# SCH_FletchVR_2024-06-24.net
KiCad netlist of a schematic drawn in EasyEDA
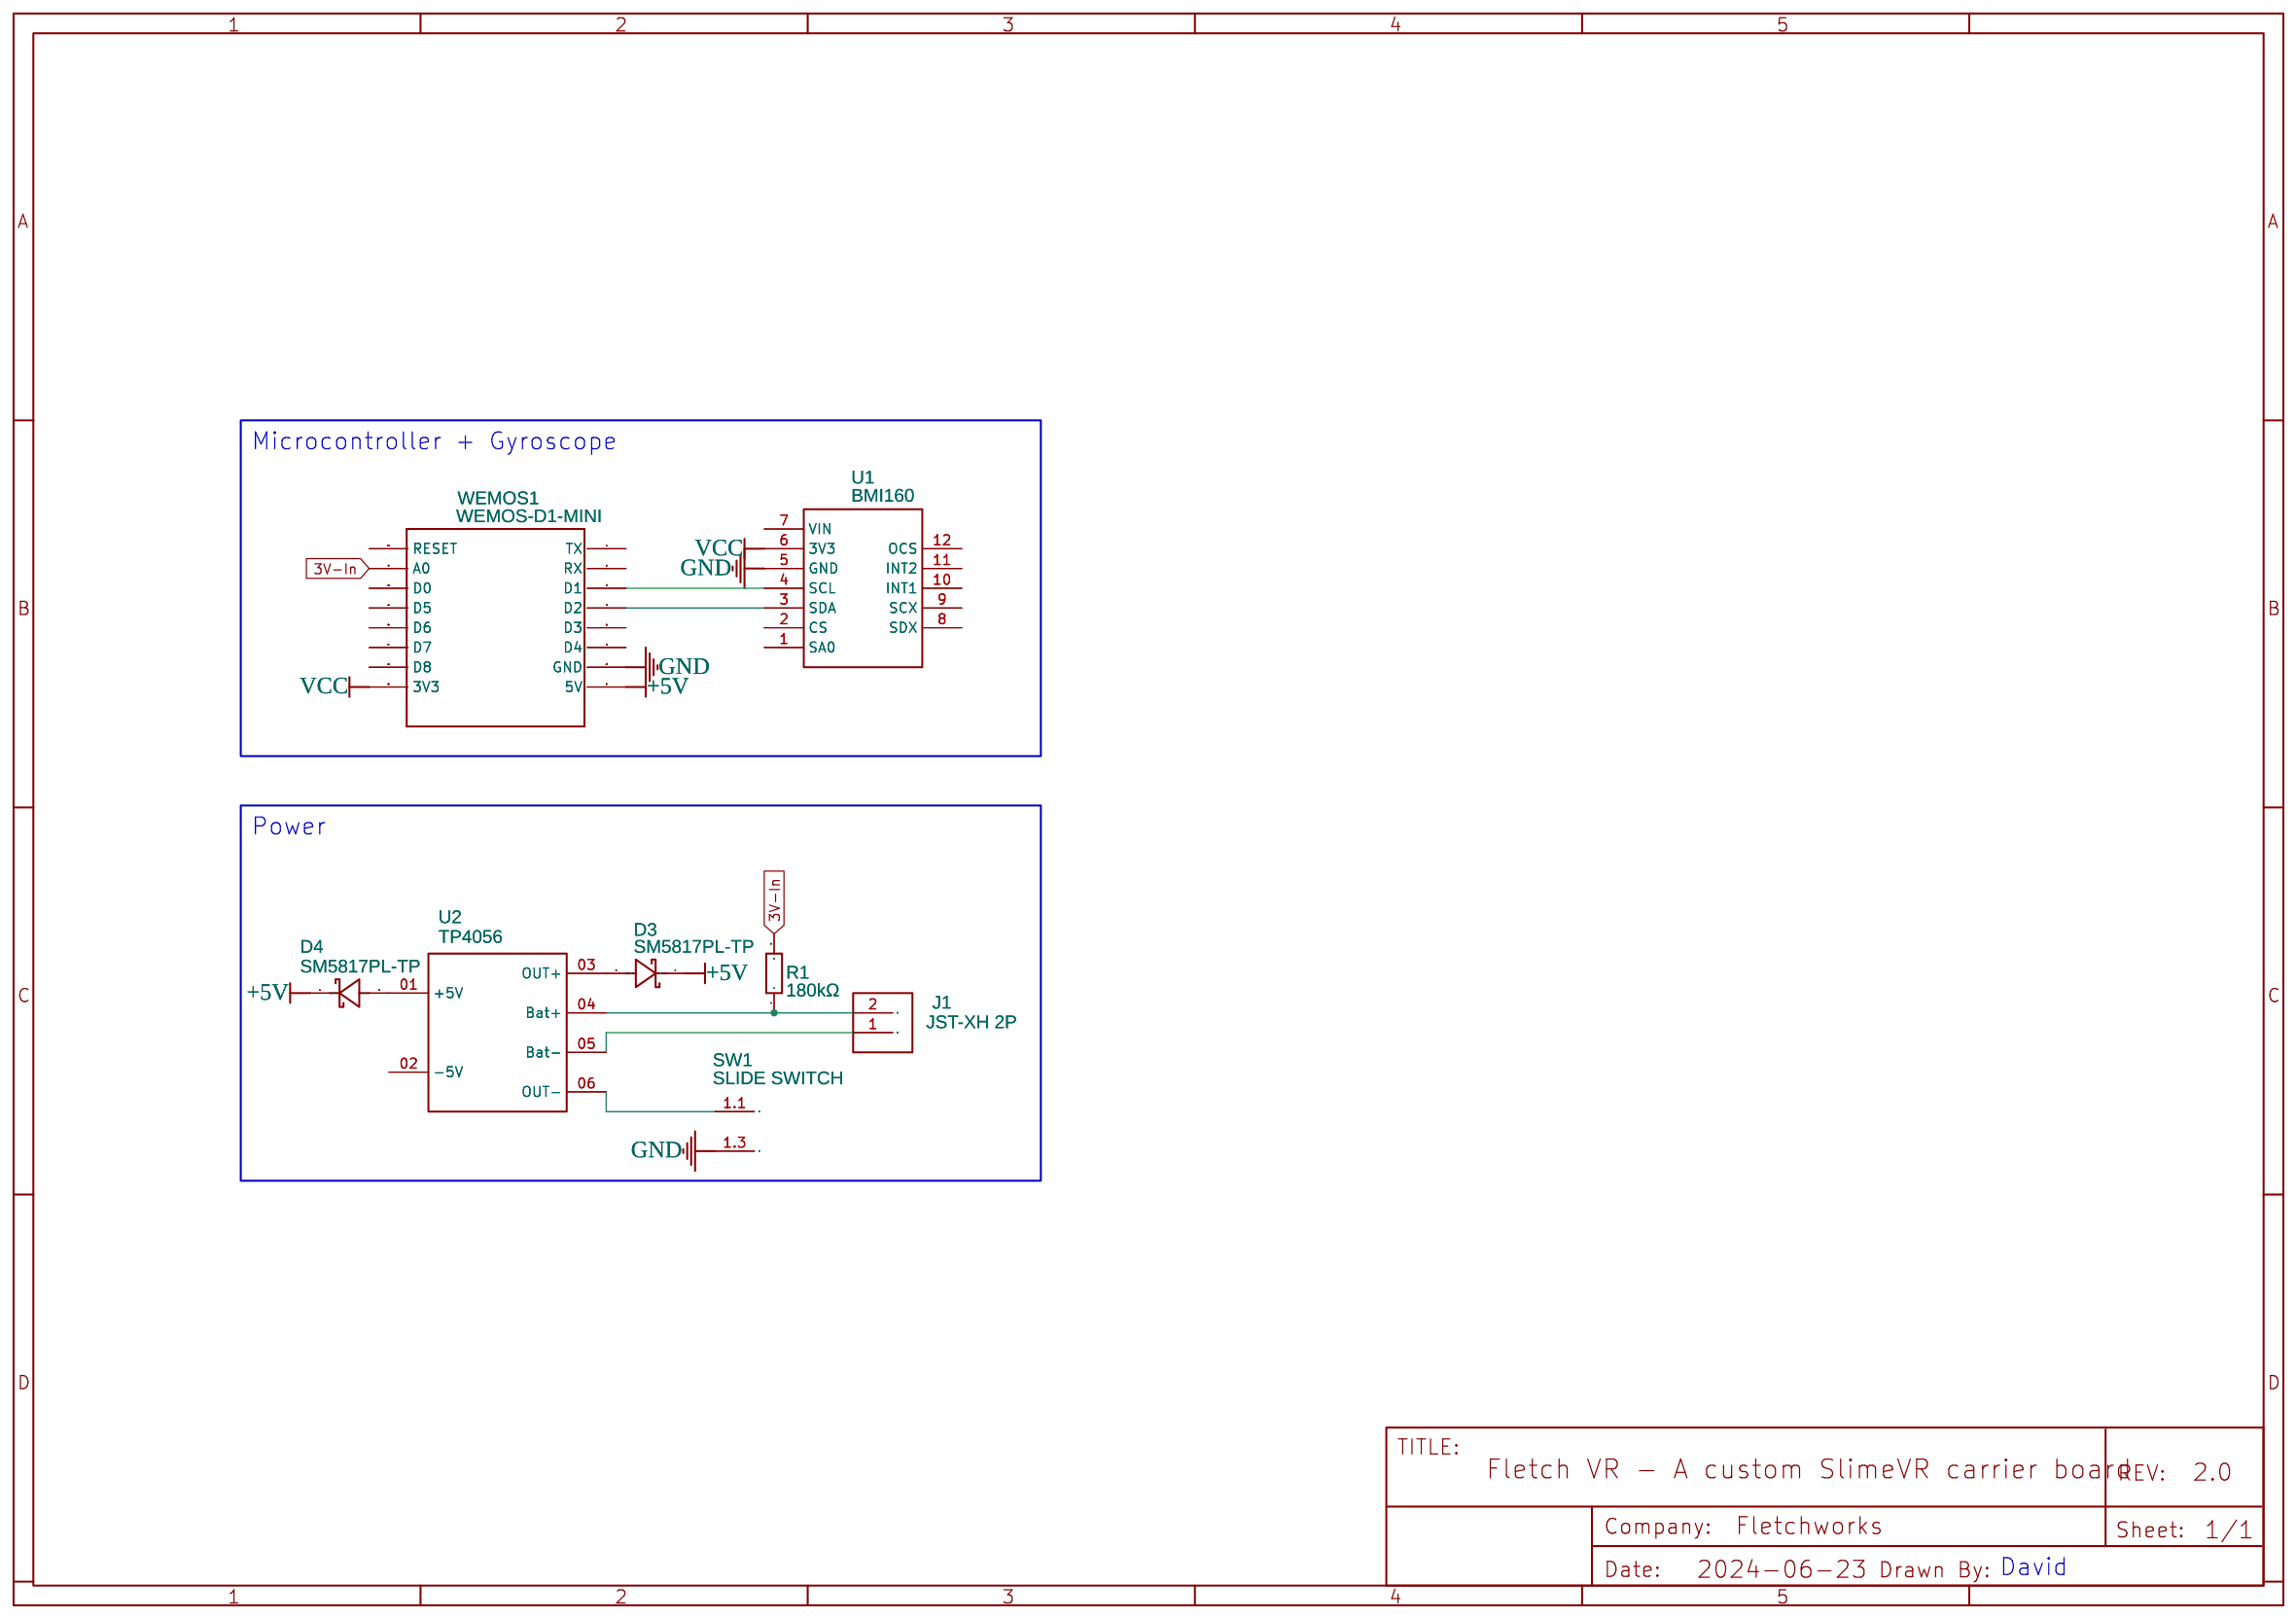
[diagram p0: schematic sheet]

(export (version "E")
  (design (tool "Eeschema 10.0.6"))
  (components
    (comp (ref "D3")
      (value "SM5817PL-TP")
      (fields (field (name "Manufacturer") "MCC(美微科)"))
      (libsource (lib "") (part "SM5817PL-TP"))
    )
    (comp (ref "D4")
      (value "SM5817PL-TP")
      (fields (field (name "Manufacturer") "MCC(美微科)"))
      (libsource (lib "") (part "SM5817PL-TP_1"))
    )
    (comp (ref "J1") (value "JST-XH 2P") (libsource (lib "") (part "JST-XH 2P")))
    (comp (ref "R1")
      (value "180kΩ")
      (fields
        (field (name "Manufacturer Part") "RMCF0402JT180K")
        (field (name "Manufacturer") "SEI(Stackpole Electronics Inc.)")
      )
      (libsource (lib "") (part "RMCF0402JT180K"))
    )
    (comp (ref "SW1")
      (value "SLIDE SWITCH")
      (fields (field (name "Manufacturer Part") "SS22F32"))
      (libsource (lib "") (part "SLIDE SWITCH 2P2T - SS22F32 PCB SLIME"))
    )
    (comp (ref "U1") (value "BMI160") (libsource (lib "") (part "BMI160")))
    (comp (ref "U2") (value "TP4056") (libsource (lib "") (part "TP4056 Symbole (modul)")))
    (comp (ref "WEMOS1") (value "WEMOS-D1-MINI") (libsource (lib "") (part "WEMOS-D1-MINI")))
  )
  (nets
    (net (code "1") (name "+5V") (class "Default")
      (node (ref "D3") (pin "1") (pinfunction "C_1") (pintype "unspecified"))
      (node (ref "D4") (pin "1") (pinfunction "C_1") (pintype "unspecified"))
      (node (ref "WEMOS1") (pin "5V") (pinfunction "5V_5V") (pintype "bidirectional"))
    )
    (net (code "2") (name "3V-In") (class "Default")
      (node (ref "R1") (pin "2") (pinfunction "2_2") (pintype "unspecified"))
      (node (ref "WEMOS1") (pin "A0") (pinfunction "A0_A0") (pintype "bidirectional"))
    )
    (net (code "3") (name "GND") (class "Default")
      (node (ref "SW1") (pin "1.3") (pinfunction "2_1.3") (pintype "unspecified"))
      (node (ref "U1") (pin "5") (pinfunction "GND_5") (pintype "unspecified"))
      (node (ref "WEMOS1") (pin "GND") (pinfunction "GND_GND") (pintype "bidirectional"))
    )
    (net (code "4") (name "Net-(D3-A)") (class "Default")
      (node (ref "D3") (pin "2") (pinfunction "A_2") (pintype "unspecified"))
      (node (ref "U2") (pin "03") (pinfunction "OUT+_03") (pintype "unspecified"))
    )
    (net (code "5") (name "Net-(D4-A)") (class "Default")
      (node (ref "D4") (pin "2") (pinfunction "A_2") (pintype "unspecified"))
      (node (ref "U2") (pin "01") (pinfunction "+5V_01") (pintype "unspecified"))
    )
    (net (code "6") (name "Net-(SW1-1)") (class "Default")
      (node (ref "SW1") (pin "1.1") (pinfunction "1_1.1") (pintype "unspecified"))
      (node (ref "U2") (pin "06") (pinfunction "OUT-_06") (pintype "unspecified"))
    )
    (net (code "7") (name "Net-(U1-SCL)") (class "Default")
      (node (ref "U1") (pin "4") (pinfunction "SCL_4") (pintype "unspecified"))
      (node (ref "WEMOS1") (pin "D1") (pinfunction "D1_D1") (pintype "bidirectional"))
    )
    (net (code "8") (name "Net-(U1-SDA)") (class "Default")
      (node (ref "U1") (pin "3") (pinfunction "SDA_3") (pintype "unspecified"))
      (node (ref "WEMOS1") (pin "D2") (pinfunction "D2_D2") (pintype "bidirectional"))
    )
    (net (code "9") (name "Net-(U2-Bat+)") (class "Default")
      (node (ref "J1") (pin "2") (pinfunction "2_2") (pintype "unspecified"))
      (node (ref "R1") (pin "1") (pinfunction "1_1") (pintype "unspecified"))
      (node (ref "U2") (pin "04") (pinfunction "Bat+_04") (pintype "unspecified"))
    )
    (net (code "10") (name "Net-(U2-Bat-)") (class "Default")
      (node (ref "J1") (pin "1") (pinfunction "1_1") (pintype "unspecified"))
      (node (ref "U2") (pin "05") (pinfunction "Bat-_05") (pintype "unspecified"))
    )
    (net (code "11") (name "VCC") (class "Default")
      (node (ref "U1") (pin "6") (pinfunction "3V3_6") (pintype "unspecified"))
      (node (ref "WEMOS1") (pin "3V3") (pinfunction "3V3_3V3") (pintype "bidirectional"))
    )
    (net (code "12") (name "unconnected-(U1-CS-Pad2)") (class "Default")
      (node (ref "U1") (pin "2") (pinfunction "CS_2") (pintype "unspecified"))
    )
    (net (code "13") (name "unconnected-(U1-INT1-Pad10)") (class "Default")
      (node (ref "U1") (pin "10") (pinfunction "INT1_10") (pintype "unspecified"))
    )
    (net (code "14") (name "unconnected-(U1-INT2-Pad11)") (class "Default")
      (node (ref "U1") (pin "11") (pinfunction "INT2_11") (pintype "unspecified"))
    )
    (net (code "15") (name "unconnected-(U1-OCS-Pad12)") (class "Default")
      (node (ref "U1") (pin "12") (pinfunction "OCS_12") (pintype "unspecified"))
    )
    (net (code "16") (name "unconnected-(U1-SA0-Pad1)") (class "Default")
      (node (ref "U1") (pin "1") (pinfunction "SA0_1") (pintype "unspecified"))
    )
    (net (code "17") (name "unconnected-(U1-SCX-Pad9)") (class "Default")
      (node (ref "U1") (pin "9") (pinfunction "SCX_9") (pintype "unspecified"))
    )
    (net (code "18") (name "unconnected-(U1-SDX-Pad8)") (class "Default")
      (node (ref "U1") (pin "8") (pinfunction "SDX_8") (pintype "unspecified"))
    )
    (net (code "19") (name "unconnected-(U1-VIN-Pad7)") (class "Default")
      (node (ref "U1") (pin "7") (pinfunction "VIN_7") (pintype "unspecified"))
    )
    (net (code "20") (name "unconnected-(U2--5V-Pad02)") (class "Default")
      (node (ref "U2") (pin "02") (pinfunction "-5V_02") (pintype "unspecified"))
    )
    (net (code "21") (name "unconnected-(WEMOS1-PadD0)") (class "Default")
      (node (ref "WEMOS1") (pin "D0") (pinfunction "D0_D0") (pintype "bidirectional"))
    )
    (net (code "22") (name "unconnected-(WEMOS1-PadD3)") (class "Default")
      (node (ref "WEMOS1") (pin "D3") (pinfunction "D3_D3") (pintype "bidirectional"))
    )
    (net (code "23") (name "unconnected-(WEMOS1-PadD4)") (class "Default")
      (node (ref "WEMOS1") (pin "D4") (pinfunction "D4_D4") (pintype "bidirectional"))
    )
    (net (code "24") (name "unconnected-(WEMOS1-PadD5)") (class "Default")
      (node (ref "WEMOS1") (pin "D5") (pinfunction "D5_D5") (pintype "bidirectional"))
    )
    (net (code "25") (name "unconnected-(WEMOS1-PadD6)") (class "Default")
      (node (ref "WEMOS1") (pin "D6") (pinfunction "D6_D6") (pintype "bidirectional"))
    )
    (net (code "26") (name "unconnected-(WEMOS1-PadD7)") (class "Default")
      (node (ref "WEMOS1") (pin "D7") (pinfunction "D7_D7") (pintype "bidirectional"))
    )
    (net (code "27") (name "unconnected-(WEMOS1-PadD8)") (class "Default")
      (node (ref "WEMOS1") (pin "D8") (pinfunction "D8_D8") (pintype "bidirectional"))
    )
    (net (code "28") (name "unconnected-(WEMOS1-PadRESET)") (class "Default")
      (node (ref "WEMOS1") (pin "RESET") (pinfunction "RESET_RESET") (pintype "bidirectional"))
    )
    (net (code "29") (name "unconnected-(WEMOS1-PadRX)") (class "Default")
      (node (ref "WEMOS1") (pin "RX") (pinfunction "RX_RX") (pintype "bidirectional"))
    )
    (net (code "30") (name "unconnected-(WEMOS1-PadTX)") (class "Default")
      (node (ref "WEMOS1") (pin "TX") (pinfunction "TX_TX") (pintype "bidirectional"))
    )
  )
)
